# interstage_A1v2.net
KiCad netlist of a schematic drawn in EAGLE
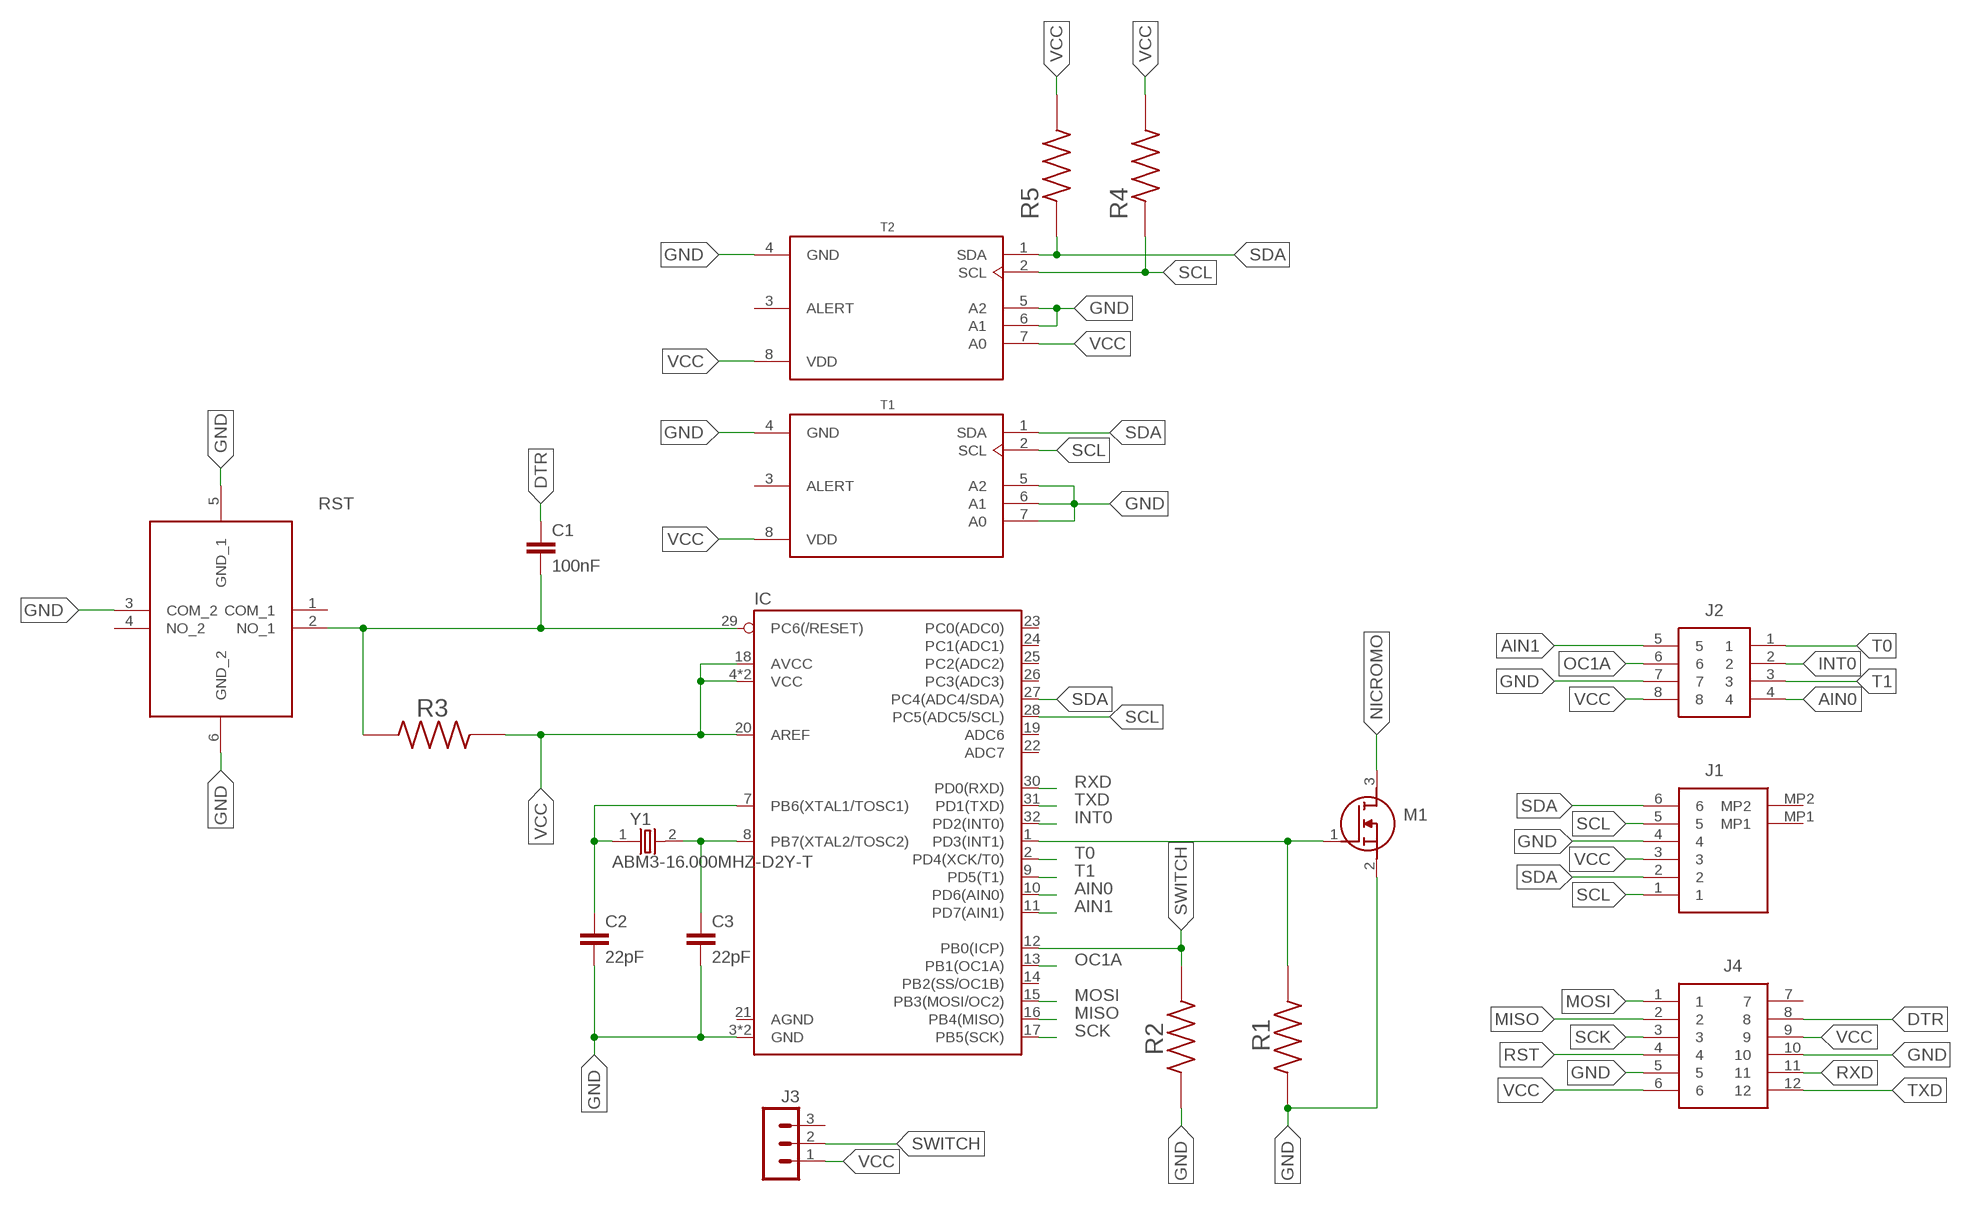
[diagram p0: schematic, sheet 1]

(export (version "E")
  (design (tool "Eeschema 10.0.6"))
  (components
    (comp (ref "C1")
      (value "100nF")
      (footprint "eagle-import:C0805K")
      (libsource (lib "eagle-import") (part "C-EUC0805K"))
    )
    (comp (ref "C2")
      (value "22pF")
      (footprint "eagle-import:C0603K")
      (libsource (lib "eagle-import") (part "C-EUC0603K"))
    )
    (comp (ref "C3")
      (value "22pF")
      (footprint "eagle-import:C0603K")
      (libsource (lib "eagle-import") (part "C-EUC0603K"))
    )
    (comp (ref "IC")
      (value "ATMEGA328P_TQFP")
      (footprint "eagle-import:TQFP32-08")
      (libsource (lib "eagle-import") (part "ATMEGA328P_TQFP"))
    )
    (comp (ref "J1")
      (value "53261-7006")
      (footprint "eagle-import:532617006")
      (fields (field (name "MOUSER_PART_NUMBER") "538-53261-7006"))
      (libsource (lib "eagle-import") (part "53261-7006"))
    )
    (comp (ref "J2")
      (value "53261-0871")
      (footprint "eagle-import:53261-0871")
      (fields (field (name "MOUSER_PART_NUMBER") "538-53261-0871"))
      (libsource (lib "eagle-import") (part "53261-0871"))
    )
    (comp (ref "J3")
      (value "MA03-1")
      (footprint "eagle-import:MA03-1")
      (libsource (lib "eagle-import") (part "MA03-1"))
    )
    (comp (ref "J4")
      (value "53261-1271")
      (footprint "eagle-import:53261-1271")
      (fields (field (name "MOUSER_PART_NUMBER") "538-53261-1271"))
      (libsource (lib "eagle-import") (part "53261-1271"))
    )
    (comp (ref "M1")
      (value "PMV16XNR")
      (footprint "eagle-import:SOT95P230X110-3N")
      (fields (field (name "MOUSER_PART_NUMBER") "771-PMV16XNR"))
      (libsource (lib "eagle-import") (part "PMV16XNR"))
    )
    (comp (ref "R1")
      (value "330")
      (footprint "eagle-import:RESC3216X70N")
      (fields
        (field (name "DIGI-KEY_PART_NUMBER") "P330BCCT-ND")
        (field (name "MF") "Panasonic Electronic")
        (field (name "MP") "ERA-8AEB331V")
      )
      (libsource (lib "eagle-import") (part "ERA-8AEB331V"))
    )
    (comp (ref "R2")
      (value "330")
      (footprint "eagle-import:RESC3216X70N")
      (fields
        (field (name "DIGI-KEY_PART_NUMBER") "P330BCCT-ND")
        (field (name "MF") "Panasonic Electronic")
        (field (name "MP") "ERA-8AEB331V")
      )
      (libsource (lib "eagle-import") (part "ERA-8AEB331V"))
    )
    (comp (ref "R3")
      (value "10k")
      (footprint "eagle-import:RESC3216X70N")
      (fields
        (field (name "DIGI-KEY_PART_NUMBER") "P10KBCCT-ND")
        (field (name "MF") "Panasonic Electronic Components")
        (field (name "MP") "ERA-8AEB103V")
      )
      (libsource (lib "eagle-import") (part "ERA-8AEB103V"))
    )
    (comp (ref "R4")
      (value "4.7k")
      (footprint "eagle-import:RESC3216X70N")
      (fields
        (field (name "DIGI-KEY_PART_NUMBER") "P4.7KBCCT-ND")
        (field (name "MF") "Panasonic")
        (field (name "MP") "ERA-8AEB472V")
      )
      (libsource (lib "eagle-import") (part "ERA-8AEB472V"))
    )
    (comp (ref "R5")
      (value "4.7k")
      (footprint "eagle-import:RESC3216X70N")
      (fields
        (field (name "DIGI-KEY_PART_NUMBER") "P4.7KBCCT-ND")
        (field (name "MF") "Panasonic")
        (field (name "MP") "ERA-8AEB472V")
      )
      (libsource (lib "eagle-import") (part "ERA-8AEB472V"))
    )
    (comp (ref "RST")
      (value "431151015826")
      (footprint "eagle-import:431151015826")
      (fields (field (name "MOUSER_PART_NUMBER") "710-431151015826"))
      (libsource (lib "eagle-import") (part "431151015826"))
    )
    (comp (ref "T1")
      (value "MCP9808T-E/MS")
      (footprint "eagle-import:SOP65P490X110-8N")
      (fields (field (name "DIGI-KEY_PART_NUMBER") "MCP9808T-E/MSCT-ND") (field (name "MF") "Microchip"))
      (libsource (lib "eagle-import") (part "MCP9808T-E/MS"))
    )
    (comp (ref "T2")
      (value "MCP9808T-E/MS")
      (footprint "eagle-import:SOP65P490X110-8N")
      (fields (field (name "DIGI-KEY_PART_NUMBER") "MCP9808T-E/MSCT-ND") (field (name "MF") "Microchip"))
      (libsource (lib "eagle-import") (part "MCP9808T-E/MS"))
    )
    (comp (ref "Y1")
      (value "ABM3-16.000MHZ-D2Y-T")
      (footprint "eagle-import:XTAL500X320X130N")
      (fields (field (name "DIGI-KEY_PART_NUMBER") "535-10638-1-ND") (field (name "MF") "Abracon"))
      (libsource (lib "eagle-import") (part "ABM3-16.000MHZ-D2Y-T"))
    )
  )
  (nets
    (net (code "1") (name "AIN0") (class "Default")
      (node (ref "IC") (pin "10") (pinfunction "PD6(AIN0)_10") (pintype "bidirectional"))
      (node (ref "J2") (pin "4") (pinfunction "4_4") (pintype "bidirectional"))
    )
    (net (code "2") (name "AIN1") (class "Default")
      (node (ref "IC") (pin "11") (pinfunction "PD7(AIN1)_11") (pintype "bidirectional"))
      (node (ref "J2") (pin "5") (pinfunction "5_5") (pintype "bidirectional"))
    )
    (net (code "3") (name "DTR") (class "Default")
      (node (ref "C1") (pin "1") (pinfunction "1_1") (pintype "passive"))
      (node (ref "J4") (pin "8") (pinfunction "8_8") (pintype "bidirectional"))
    )
    (net (code "4") (name "GND") (class "Default")
      (node (ref "C2") (pin "2") (pinfunction "2_2") (pintype "passive"))
      (node (ref "C3") (pin "2") (pinfunction "2_2") (pintype "passive"))
      (node (ref "IC") (pin "3") (pinfunction "GND_3") (pintype "bidirectional"))
      (node (ref "IC") (pin "5") (pinfunction "GND_5") (pintype "bidirectional"))
      (node (ref "J1") (pin "4") (pinfunction "4_4") (pintype "bidirectional"))
      (node (ref "J2") (pin "7") (pinfunction "7_7") (pintype "bidirectional"))
      (node (ref "J4") (pin "10") (pinfunction "10_10") (pintype "bidirectional"))
      (node (ref "J4") (pin "5") (pinfunction "5_5") (pintype "bidirectional"))
      (node (ref "M1") (pin "2") (pinfunction "S_2") (pintype "bidirectional"))
      (node (ref "R1") (pin "2") (pinfunction "2_2") (pintype "passive"))
      (node (ref "R2") (pin "1") (pinfunction "1_1") (pintype "passive"))
      (node (ref "RST") (pin "3") (pinfunction "COM_2_3") (pintype "bidirectional"))
      (node (ref "RST") (pin "5") (pinfunction "GND_1_5") (pintype "bidirectional"))
      (node (ref "RST") (pin "6") (pinfunction "GND_2_6") (pintype "bidirectional"))
      (node (ref "T1") (pin "4") (pinfunction "GND_4") (pintype "power_in"))
      (node (ref "T1") (pin "5") (pinfunction "A2_5") (pintype "input"))
      (node (ref "T1") (pin "6") (pinfunction "A1_6") (pintype "input"))
      (node (ref "T1") (pin "7") (pinfunction "A0_7") (pintype "input"))
      (node (ref "T2") (pin "4") (pinfunction "GND_4") (pintype "power_in"))
      (node (ref "T2") (pin "5") (pinfunction "A2_5") (pintype "input"))
      (node (ref "T2") (pin "6") (pinfunction "A1_6") (pintype "input"))
    )
    (net (code "5") (name "INT0") (class "Default")
      (node (ref "IC") (pin "32") (pinfunction "PD2(INT0)_32") (pintype "bidirectional"))
      (node (ref "J2") (pin "2") (pinfunction "2_2") (pintype "bidirectional"))
    )
    (net (code "6") (name "MISO") (class "Default")
      (node (ref "IC") (pin "16") (pinfunction "PB4(MISO)_16") (pintype "bidirectional"))
      (node (ref "J4") (pin "2") (pinfunction "2_2") (pintype "bidirectional"))
    )
    (net (code "7") (name "MOSI") (class "Default")
      (node (ref "IC") (pin "15") (pinfunction "PB3(MOSI/OC2)_15") (pintype "bidirectional"))
      (node (ref "J4") (pin "1") (pinfunction "1_1") (pintype "bidirectional"))
    )
    (net (code "8") (name "NICROMO") (class "Default")
      (node (ref "M1") (pin "3") (pinfunction "D_3") (pintype "bidirectional"))
    )
    (net (code "9") (name "Net-(IC-PB6(XTAL1{slash}TOSC1))") (class "Default")
      (node (ref "C2") (pin "1") (pinfunction "1_1") (pintype "passive"))
      (node (ref "IC") (pin "7") (pinfunction "PB6(XTAL1/TOSC1)_7") (pintype "bidirectional"))
      (node (ref "Y1") (pin "1") (pinfunction "1_1") (pintype "passive"))
    )
    (net (code "10") (name "Net-(IC-PB7(XTAL2{slash}TOSC2))") (class "Default")
      (node (ref "C3") (pin "1") (pinfunction "1_1") (pintype "passive"))
      (node (ref "IC") (pin "8") (pinfunction "PB7(XTAL2/TOSC2)_8") (pintype "bidirectional"))
      (node (ref "Y1") (pin "2") (pinfunction "2_2") (pintype "passive"))
    )
    (net (code "11") (name "Net-(IC-PD3(INT1))") (class "Default")
      (node (ref "IC") (pin "1") (pinfunction "PD3(INT1)_1") (pintype "bidirectional"))
      (node (ref "M1") (pin "1") (pinfunction "G_1") (pintype "bidirectional"))
      (node (ref "R1") (pin "1") (pinfunction "1_1") (pintype "passive"))
    )
    (net (code "12") (name "OC1A") (class "Default")
      (node (ref "IC") (pin "13") (pinfunction "PB1(OC1A)_13") (pintype "bidirectional"))
      (node (ref "J2") (pin "6") (pinfunction "6_6") (pintype "bidirectional"))
    )
    (net (code "13") (name "RST") (class "Default")
      (node (ref "C1") (pin "2") (pinfunction "2_2") (pintype "passive"))
      (node (ref "IC") (pin "29") (pinfunction "PC6(/RESET)_29") (pintype "bidirectional"))
      (node (ref "J4") (pin "4") (pinfunction "4_4") (pintype "bidirectional"))
      (node (ref "R3") (pin "1") (pinfunction "1_1") (pintype "passive"))
      (node (ref "RST") (pin "2") (pinfunction "NO_1_2") (pintype "bidirectional"))
    )
    (net (code "14") (name "RXD") (class "Default")
      (node (ref "IC") (pin "30") (pinfunction "PD0(RXD)_30") (pintype "bidirectional"))
      (node (ref "J4") (pin "11") (pinfunction "11_11") (pintype "bidirectional"))
    )
    (net (code "15") (name "SCK") (class "Default")
      (node (ref "IC") (pin "17") (pinfunction "PB5(SCK)_17") (pintype "bidirectional"))
      (node (ref "J4") (pin "3") (pinfunction "3_3") (pintype "bidirectional"))
    )
    (net (code "16") (name "SCL") (class "Default")
      (node (ref "IC") (pin "28") (pinfunction "PC5(ADC5/SCL)_28") (pintype "bidirectional"))
      (node (ref "J1") (pin "1") (pinfunction "1_1") (pintype "bidirectional"))
      (node (ref "J1") (pin "5") (pinfunction "5_5") (pintype "bidirectional"))
      (node (ref "R4") (pin "1") (pinfunction "1_1") (pintype "passive"))
      (node (ref "T1") (pin "2") (pinfunction "SCL_2") (pintype "input"))
      (node (ref "T2") (pin "2") (pinfunction "SCL_2") (pintype "input"))
    )
    (net (code "17") (name "SDA") (class "Default")
      (node (ref "IC") (pin "27") (pinfunction "PC4(ADC4/SDA)_27") (pintype "bidirectional"))
      (node (ref "J1") (pin "2") (pinfunction "2_2") (pintype "bidirectional"))
      (node (ref "J1") (pin "6") (pinfunction "6_6") (pintype "bidirectional"))
      (node (ref "R5") (pin "1") (pinfunction "1_1") (pintype "passive"))
      (node (ref "T1") (pin "1") (pinfunction "SDA_1") (pintype "bidirectional"))
      (node (ref "T2") (pin "1") (pinfunction "SDA_1") (pintype "bidirectional"))
    )
    (net (code "18") (name "SWITCH") (class "Default")
      (node (ref "IC") (pin "12") (pinfunction "PB0(ICP)_12") (pintype "bidirectional"))
      (node (ref "J3") (pin "2") (pinfunction "2_2") (pintype "passive"))
      (node (ref "R2") (pin "2") (pinfunction "2_2") (pintype "passive"))
    )
    (net (code "19") (name "T0") (class "Default")
      (node (ref "IC") (pin "2") (pinfunction "PD4(XCK/T0)_2") (pintype "bidirectional"))
      (node (ref "J2") (pin "1") (pinfunction "1_1") (pintype "bidirectional"))
    )
    (net (code "20") (name "T1") (class "Default")
      (node (ref "IC") (pin "9") (pinfunction "PD5(T1)_9") (pintype "bidirectional"))
      (node (ref "J2") (pin "3") (pinfunction "3_3") (pintype "bidirectional"))
    )
    (net (code "21") (name "TXD") (class "Default")
      (node (ref "IC") (pin "31") (pinfunction "PD1(TXD)_31") (pintype "bidirectional"))
      (node (ref "J4") (pin "12") (pinfunction "12_12") (pintype "bidirectional"))
    )
    (net (code "22") (name "VCC") (class "Default")
      (node (ref "IC") (pin "18") (pinfunction "AVCC_18") (pintype "bidirectional"))
      (node (ref "IC") (pin "20") (pinfunction "AREF_20") (pintype "bidirectional"))
      (node (ref "IC") (pin "4") (pinfunction "VCC_4") (pintype "bidirectional"))
      (node (ref "IC") (pin "6") (pinfunction "VCC_6") (pintype "bidirectional"))
      (node (ref "J1") (pin "3") (pinfunction "3_3") (pintype "bidirectional"))
      (node (ref "J2") (pin "8") (pinfunction "8_8") (pintype "bidirectional"))
      (node (ref "J3") (pin "1") (pinfunction "1_1") (pintype "passive"))
      (node (ref "J4") (pin "6") (pinfunction "6_6") (pintype "bidirectional"))
      (node (ref "J4") (pin "9") (pinfunction "9_9") (pintype "bidirectional"))
      (node (ref "R3") (pin "2") (pinfunction "2_2") (pintype "passive"))
      (node (ref "R4") (pin "2") (pinfunction "2_2") (pintype "passive"))
      (node (ref "R5") (pin "2") (pinfunction "2_2") (pintype "passive"))
      (node (ref "T1") (pin "8") (pinfunction "VDD_8") (pintype "power_in"))
      (node (ref "T2") (pin "7") (pinfunction "A0_7") (pintype "input"))
      (node (ref "T2") (pin "8") (pinfunction "VDD_8") (pintype "power_in"))
    )
    (net (code "23") (name "unconnected-(IC-ADC6-Pad19)") (class "Default")
      (node (ref "IC") (pin "19") (pinfunction "ADC6_19") (pintype "bidirectional"))
    )
    (net (code "24") (name "unconnected-(IC-ADC7-Pad22)") (class "Default")
      (node (ref "IC") (pin "22") (pinfunction "ADC7_22") (pintype "bidirectional"))
    )
    (net (code "25") (name "unconnected-(IC-AGND-Pad21)") (class "Default")
      (node (ref "IC") (pin "21") (pinfunction "AGND_21") (pintype "bidirectional"))
    )
    (net (code "26") (name "unconnected-(IC-PB2(SS{slash}OC1B)-Pad14)") (class "Default")
      (node (ref "IC") (pin "14") (pinfunction "PB2(SS/OC1B)_14") (pintype "bidirectional"))
    )
    (net (code "27") (name "unconnected-(IC-PC0(ADC0)-Pad23)") (class "Default")
      (node (ref "IC") (pin "23") (pinfunction "PC0(ADC0)_23") (pintype "bidirectional"))
    )
    (net (code "28") (name "unconnected-(IC-PC1(ADC1)-Pad24)") (class "Default")
      (node (ref "IC") (pin "24") (pinfunction "PC1(ADC1)_24") (pintype "bidirectional"))
    )
    (net (code "29") (name "unconnected-(IC-PC2(ADC2)-Pad25)") (class "Default")
      (node (ref "IC") (pin "25") (pinfunction "PC2(ADC2)_25") (pintype "bidirectional"))
    )
    (net (code "30") (name "unconnected-(IC-PC3(ADC3)-Pad26)") (class "Default")
      (node (ref "IC") (pin "26") (pinfunction "PC3(ADC3)_26") (pintype "bidirectional"))
    )
    (net (code "31") (name "unconnected-(J1-PadMP1)") (class "Default")
      (node (ref "J1") (pin "MP1") (pinfunction "MP1_MP1") (pintype "bidirectional"))
    )
    (net (code "32") (name "unconnected-(J1-PadMP2)") (class "Default")
      (node (ref "J1") (pin "MP2") (pinfunction "MP2_MP2") (pintype "bidirectional"))
    )
    (net (code "33") (name "unconnected-(J3-Pad3)") (class "Default")
      (node (ref "J3") (pin "3") (pinfunction "3_3") (pintype "passive"))
    )
    (net (code "34") (name "unconnected-(J4-Pad7)") (class "Default")
      (node (ref "J4") (pin "7") (pinfunction "7_7") (pintype "bidirectional"))
    )
    (net (code "35") (name "unconnected-(RST-COM_1-Pad1)") (class "Default")
      (node (ref "RST") (pin "1") (pinfunction "COM_1_1") (pintype "bidirectional"))
    )
    (net (code "36") (name "unconnected-(RST-NO_2-Pad4)") (class "Default")
      (node (ref "RST") (pin "4") (pinfunction "NO_2_4") (pintype "bidirectional"))
    )
    (net (code "37") (name "unconnected-(T1-ALERT-Pad3)") (class "Default")
      (node (ref "T1") (pin "3") (pinfunction "ALERT_3") (pintype "output"))
    )
    (net (code "38") (name "unconnected-(T2-ALERT-Pad3)") (class "Default")
      (node (ref "T2") (pin "3") (pinfunction "ALERT_3") (pintype "output"))
    )
  )
)
